# mcu.net
KiCad netlist of a schematic drawn in Altium Designer
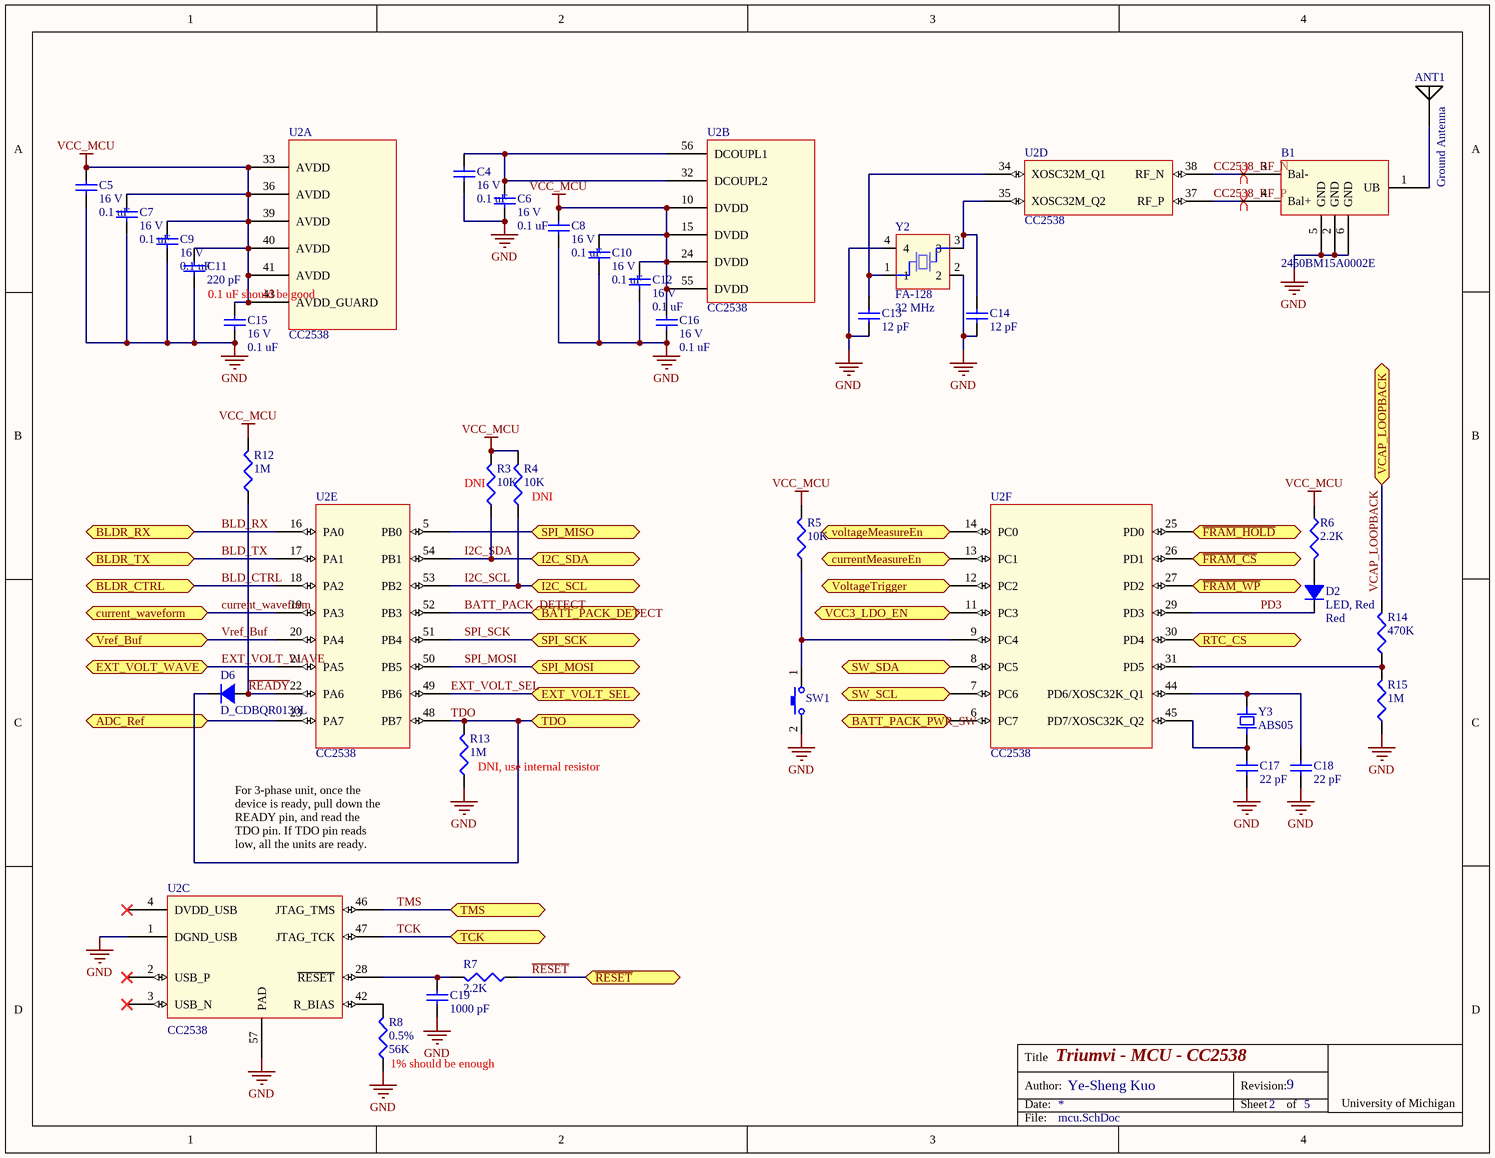
[diagram p0: mcu.SchDoc]

(export (version "E")
  (design (tool "Eeschema 10.0.6"))
  (components
    (comp (ref "ANT1")
      (value "Ground Antenna")
      (footprint "Chip Antenna")
      (description "2.4GHz Surface Mount Device (SMD) On Ground Antenna, 50 Ohms")
      (libsource (lib "RF") (part "Ground Antenna"))
    )
    (comp (ref "B1")
      (value "2450BM15A0002E")
      (footprint "2450BM15A0002")
      (description "2.45 GHz Balun for TI CC253X")
      (libsource (lib "RF") (part "2450BM15A0002E"))
    )
    (comp (ref "C4")
      (value "0.1 uF")
      (footprint "0402")
      (description "Ceramic capacitor, 0.1u, 16 V, 0402 package")
      (fields
        (field (name "VOLTAGE RATED") "16 V")
        (field (name "TOLERANCE") "10%")
        (field (name "Comment") "Ceramic capacitor")
      )
      (libsource (lib "rlc") (part "C_0.1u_16V_0402_ceramic"))
    )
    (comp (ref "C5")
      (value "0.1 uF")
      (footprint "0402")
      (description "Ceramic capacitor, 0.1u, 16 V, 0402 package")
      (fields
        (field (name "VOLTAGE RATED") "16 V")
        (field (name "TOLERANCE") "10%")
        (field (name "Comment") "Ceramic capacitor")
      )
      (libsource (lib "rlc") (part "C_0.1u_16V_0402_ceramic"))
    )
    (comp (ref "C6")
      (value "0.1 uF")
      (footprint "0402")
      (description "Ceramic capacitor, 0.1u, 16 V, 0402 package")
      (fields
        (field (name "VOLTAGE RATED") "16 V")
        (field (name "TOLERANCE") "10%")
        (field (name "Comment") "Ceramic capacitor")
      )
      (libsource (lib "rlc") (part "C_0.1u_16V_0402_ceramic"))
    )
    (comp (ref "C7")
      (value "0.1 uF")
      (footprint "0402")
      (description "Ceramic capacitor, 0.1u, 16 V, 0402 package")
      (fields
        (field (name "VOLTAGE RATED") "16 V")
        (field (name "TOLERANCE") "10%")
        (field (name "Comment") "Ceramic capacitor")
      )
      (libsource (lib "rlc") (part "C_0.1u_16V_0402_ceramic"))
    )
    (comp (ref "C8")
      (value "0.1 uF")
      (footprint "0402")
      (description "Ceramic capacitor, 0.1u, 16 V, 0402 package")
      (fields
        (field (name "VOLTAGE RATED") "16 V")
        (field (name "TOLERANCE") "10%")
        (field (name "Comment") "Ceramic capacitor")
      )
      (libsource (lib "rlc") (part "C_0.1u_16V_0402_ceramic"))
    )
    (comp (ref "C9")
      (value "0.1 uF")
      (footprint "0402")
      (description "Ceramic capacitor, 0.1u, 16 V, 0402 package")
      (fields
        (field (name "VOLTAGE RATED") "16 V")
        (field (name "TOLERANCE") "10%")
        (field (name "Comment") "Ceramic capacitor")
      )
      (libsource (lib "rlc") (part "C_0.1u_16V_0402_ceramic"))
    )
    (comp (ref "C10")
      (value "0.1 uF")
      (footprint "0402")
      (description "Ceramic capacitor, 0.1u, 16 V, 0402 package")
      (fields
        (field (name "VOLTAGE RATED") "16 V")
        (field (name "TOLERANCE") "10%")
        (field (name "Comment") "Ceramic capacitor")
      )
      (libsource (lib "rlc") (part "C_0.1u_16V_0402_ceramic"))
    )
    (comp (ref "C11")
      (value "220 pF")
      (footprint "0402")
      (description "Ceramic capacitor, 220 pF, 0402 package")
      (fields (field (name "TOLERANCE") "10%") (field (name "Comment") "Ceramic capacitor"))
      (libsource (lib "rlc") (part "C_220p_50V_0402_ceramic"))
    )
    (comp (ref "C12")
      (value "0.1 uF")
      (footprint "0402")
      (description "Ceramic capacitor, 0.1u, 16 V, 0402 package")
      (fields
        (field (name "VOLTAGE RATED") "16 V")
        (field (name "TOLERANCE") "10%")
        (field (name "Comment") "Ceramic capacitor")
      )
      (libsource (lib "rlc") (part "C_0.1u_16V_0402_ceramic"))
    )
    (comp (ref "C13")
      (value "12 pF")
      (footprint "0402")
      (description "Ceramic capacitor, 12 pF, 0402 package")
      (fields (field (name "TOLERANCE") "2%") (field (name "Comment") "Ceramic capacitor"))
      (libsource (lib "rlc") (part "C_12p_0402_ceramic"))
    )
    (comp (ref "C14")
      (value "12 pF")
      (footprint "0402")
      (description "Ceramic capacitor, 12 pF, 0402 package")
      (fields (field (name "TOLERANCE") "2%") (field (name "Comment") "Ceramic capacitor"))
      (libsource (lib "rlc") (part "C_12p_0402_ceramic"))
    )
    (comp (ref "C15")
      (value "0.1 uF")
      (footprint "0402")
      (description "Ceramic capacitor, 0.1u, 16 V, 0402 package")
      (fields
        (field (name "VOLTAGE RATED") "16 V")
        (field (name "TOLERANCE") "10%")
        (field (name "Comment") "Ceramic capacitor")
      )
      (libsource (lib "rlc") (part "C_0.1u_16V_0402_ceramic"))
    )
    (comp (ref "C16")
      (value "0.1 uF")
      (footprint "0402")
      (description "Ceramic capacitor, 0.1u, 16 V, 0402 package")
      (fields
        (field (name "VOLTAGE RATED") "16 V")
        (field (name "TOLERANCE") "10%")
        (field (name "Comment") "Ceramic capacitor")
      )
      (libsource (lib "rlc") (part "C_0.1u_16V_0402_ceramic"))
    )
    (comp (ref "C17")
      (value "22 pF")
      (footprint "0402")
      (description "Ceramic capacitor, 22 pF, 0402 package")
      (fields (field (name "TOLERANCE") "2%") (field (name "Comment") "Ceramic capacitor"))
      (libsource (lib "rlc") (part "C_22p_0402_ceramic"))
    )
    (comp (ref "C18")
      (value "22 pF")
      (footprint "0402")
      (description "Ceramic capacitor, 22 pF, 0402 package")
      (fields (field (name "TOLERANCE") "2%") (field (name "Comment") "Ceramic capacitor"))
      (libsource (lib "rlc") (part "C_22p_0402_ceramic"))
    )
    (comp (ref "C19")
      (value "1000 pF")
      (footprint "0402")
      (description "Ceramic capacitor, 1000 pF, 0402 package")
      (fields (field (name "TOLERANCE") "10%") (field (name "Comment") "Ceramic capacitor"))
      (libsource (lib "rlc") (part "C_1000p_50V_0402_ceramic"))
    )
    (comp (ref "D2")
      (value "LED, Red")
      (footprint "0402 - DIODE")
      (description "LED, Red, 0402")
      (fields (field (name "COLOR") "Red"))
      (libsource (lib "rlc") (part "D_LED_RED_0402"))
    )
    (comp (ref "D6")
      (value "D_CDBQR0130L")
      (footprint "0402 - DIODE")
      (description "SMD Schottky Barrier Diode")
      (libsource (lib "rlc") (part "D_CDBQR0130L"))
    )
    (comp (ref "R3")
      (value "10K")
      (footprint "0402")
      (description "Chip resistor, 10K, 0402 package")
      (fields (field (name "TOLERANCE") "1%") (field (name "POWER") "1/16 W"))
      (libsource (lib "rlc") (part "R_10K_0402"))
    )
    (comp (ref "R4")
      (value "10K")
      (footprint "0402")
      (description "Chip resistor, 10K, 0402 package")
      (fields (field (name "TOLERANCE") "1%") (field (name "POWER") "1/16 W"))
      (libsource (lib "rlc") (part "R_10K_0402"))
    )
    (comp (ref "R5")
      (value "10K")
      (footprint "0402")
      (description "Chip resistor, 10K, 0402 package")
      (fields (field (name "TOLERANCE") "1%") (field (name "POWER") "1/16 W"))
      (libsource (lib "rlc") (part "R_10K_0402"))
    )
    (comp (ref "R6")
      (value "2.2K")
      (footprint "0402")
      (description "Chip resistor, 2.2K, 0402 package")
      (fields (field (name "TOLERANCE") "1%") (field (name "POWER") "1/16 W"))
      (libsource (lib "rlc") (part "R_2.2K_0402"))
    )
    (comp (ref "R7")
      (value "2.2K")
      (footprint "0402")
      (description "Chip resistor, 2.2K, 0402 package")
      (fields (field (name "TOLERANCE") "1%") (field (name "POWER") "1/16 W"))
      (libsource (lib "rlc") (part "R_2.2K_0402"))
    )
    (comp (ref "R8")
      (value "56K")
      (footprint "0402")
      (description "Chip resistor, 56K, 0402 package")
      (fields
        (field (name "POWER") "1/16 W")
        (field (name "TOLERANCE") "0.5%")
        (field (name "Comment") "Chip resistor")
      )
      (libsource (lib "rlc") (part "R_56K_0402"))
    )
    (comp (ref "R12")
      (value "1M")
      (footprint "0402")
      (description "Chip resistor, 1M, 0402 package")
      (fields (field (name "TOLERANCE") "1%") (field (name "POWER") "1/16 W"))
      (libsource (lib "rlc") (part "R_1M_0402"))
    )
    (comp (ref "R13")
      (value "1M")
      (footprint "0402")
      (description "Chip resistor, 1M, 0402 package")
      (fields (field (name "TOLERANCE") "1%") (field (name "POWER") "1/16 W"))
      (libsource (lib "rlc") (part "R_1M_0402"))
    )
    (comp (ref "R14")
      (value "470K")
      (footprint "0402")
      (description "Chip resistor, 470K, 0402 package")
      (fields (field (name "TOLERANCE") "5%") (field (name "POWER") "1/16 W"))
      (libsource (lib "rlc") (part "R_470K_0402"))
    )
    (comp (ref "R15")
      (value "1M")
      (footprint "0402")
      (description "Chip resistor, 1M, 0402 package")
      (fields (field (name "TOLERANCE") "1%") (field (name "POWER") "1/16 W"))
      (libsource (lib "rlc") (part "R_1M_0402"))
    )
    (comp (ref "SW1")
      (value "EVQP7C")
      (footprint "EVQP7C")
      (description "3.5 mm×2.9 mm Side-operational SMD  Light Touch Switches")
      (libsource (lib "switches") (part "EVQP7C"))
    )
    (comp (ref "U2")
      (value "CC2538")
      (footprint "QFN56")
      (description "A Powerful System-On-Chip for 2.4-GHz IEEE 802.15.4, 6LoWPAN  and ZigBee Applications")
      (libsource (lib "mcu") (part "CC2538"))
    )
    (comp (ref "Y2")
      (value "FA-128")
      (footprint "FA-128")
      (description "MHz Range Crystal Unit")
      (fields (field (name "FREQUENCY") "32 MHz"))
      (libsource (lib "crystal_oscillators_rtc") (part "FA-128"))
    )
    (comp (ref "Y3")
      (value "ABS05")
      (footprint "ABS05")
      (description "32768 Hz SMD Low profile crystal")
      (libsource (lib "crystal_oscillators_rtc") (part "ABS05"))
    )
  )
  (nets
    (net (code "1") (name "/ADC_Ref") (class "Default")
      (node (ref "U2") (pin "23") (pinfunction "PA7_23") (pintype "bidirectional"))
    )
    (net (code "2") (name "/BATT_PACK_DETECT") (class "Default")
      (node (ref "U2") (pin "52") (pinfunction "PB3_52") (pintype "bidirectional"))
    )
    (net (code "3") (name "/BATT_PACK_PWR_SW") (class "Default")
      (node (ref "U2") (pin "6") (pinfunction "PC7_6") (pintype "bidirectional"))
    )
    (net (code "4") (name "/BLD_CTRL") (class "Default")
      (node (ref "U2") (pin "18") (pinfunction "PA2_18") (pintype "bidirectional"))
    )
    (net (code "5") (name "/BLD_RX") (class "Default")
      (node (ref "U2") (pin "16") (pinfunction "PA0_16") (pintype "bidirectional"))
    )
    (net (code "6") (name "/BLD_TX") (class "Default")
      (node (ref "U2") (pin "17") (pinfunction "PA1_17") (pintype "bidirectional"))
    )
    (net (code "7") (name "/CC2538_RF_N") (class "Default")
      (node (ref "B1") (pin "3") (pinfunction "Bal-_3") (pintype "passive"))
      (node (ref "U2") (pin "38") (pinfunction "RF_N_38") (pintype "bidirectional"))
    )
    (net (code "8") (name "/CC2538_RF_P") (class "Default")
      (node (ref "B1") (pin "4") (pinfunction "Bal+_4") (pintype "passive"))
      (node (ref "U2") (pin "37") (pinfunction "RF_P_37") (pintype "bidirectional"))
    )
    (net (code "9") (name "/EXT_VOLT_SEL") (class "Default")
      (node (ref "U2") (pin "49") (pinfunction "PB6_49") (pintype "bidirectional"))
    )
    (net (code "10") (name "/EXT_VOLT_WAVE") (class "Default")
      (node (ref "U2") (pin "21") (pinfunction "PA5_21") (pintype "bidirectional"))
    )
    (net (code "11") (name "/I2C_SCL") (class "Default")
      (node (ref "R4") (pin "2") (pintype "passive"))
      (node (ref "U2") (pin "53") (pinfunction "PB2_53") (pintype "bidirectional"))
    )
    (net (code "12") (name "/I2C_SDA") (class "Default")
      (node (ref "R3") (pin "2") (pintype "passive"))
      (node (ref "U2") (pin "54") (pinfunction "PB1_54") (pintype "bidirectional"))
    )
    (net (code "13") (name "/PD3") (class "Default")
      (node (ref "D2") (pin "2") (pintype "passive"))
      (node (ref "U2") (pin "29") (pinfunction "PD3_29") (pintype "bidirectional"))
    )
    (net (code "14") (name "/RTC_CS") (class "Default")
      (node (ref "U2") (pin "30") (pinfunction "PD4_30") (pintype "bidirectional"))
    )
    (net (code "15") (name "/SPI_MISO") (class "Default")
      (node (ref "U2") (pin "5") (pinfunction "PB0_5") (pintype "bidirectional"))
    )
    (net (code "16") (name "/SPI_MOSI") (class "Default")
      (node (ref "U2") (pin "50") (pinfunction "PB5_50") (pintype "bidirectional"))
    )
    (net (code "17") (name "/SPI_SCK") (class "Default")
      (node (ref "U2") (pin "51") (pinfunction "PB4_51") (pintype "bidirectional"))
    )
    (net (code "18") (name "/SW_SCL") (class "Default")
      (node (ref "U2") (pin "7") (pinfunction "PC6_7") (pintype "bidirectional"))
    )
    (net (code "19") (name "/SW_SDA") (class "Default")
      (node (ref "U2") (pin "8") (pinfunction "PC5_8") (pintype "bidirectional"))
    )
    (net (code "20") (name "/TCK") (class "Default")
      (node (ref "U2") (pin "47") (pinfunction "JTAG_TCK_47") (pintype "bidirectional"))
    )
    (net (code "21") (name "/TDO") (class "Default")
      (node (ref "D6") (pin "2") (pintype "passive"))
      (node (ref "R13") (pin "1") (pintype "passive"))
      (node (ref "U2") (pin "48") (pinfunction "PB7_48") (pintype "bidirectional"))
    )
    (net (code "22") (name "/TMS") (class "Default")
      (node (ref "U2") (pin "46") (pinfunction "JTAG_TMS_46") (pintype "bidirectional"))
    )
    (net (code "23") (name "/VCAP_LOOPBACK") (class "Default")
      (node (ref "R14") (pin "1") (pintype "passive"))
    )
    (net (code "24") (name "/VCC3_LDO_EN") (class "Default")
      (node (ref "U2") (pin "11") (pinfunction "PC3_11") (pintype "bidirectional"))
    )
    (net (code "25") (name "/VoltageTrigger") (class "Default")
      (node (ref "U2") (pin "12") (pinfunction "PC2_12") (pintype "bidirectional"))
    )
    (net (code "26") (name "/Vref_Buf") (class "Default")
      (node (ref "U2") (pin "20") (pinfunction "PA4_20") (pintype "bidirectional"))
    )
    (net (code "27") (name "/currentMeasureEn") (class "Default")
      (node (ref "U2") (pin "13") (pinfunction "PC1_13") (pintype "bidirectional"))
    )
    (net (code "28") (name "/current_waveform") (class "Default")
      (node (ref "U2") (pin "19") (pinfunction "PA3_19") (pintype "bidirectional"))
    )
    (net (code "29") (name "/voltageMeasureEn") (class "Default")
      (node (ref "U2") (pin "14") (pinfunction "PC0_14") (pintype "bidirectional"))
    )
    (net (code "30") (name "/~{FRAM_CS}") (class "Default")
      (node (ref "U2") (pin "26") (pinfunction "PD1_26") (pintype "bidirectional"))
    )
    (net (code "31") (name "/~{FRAM_HOLD}") (class "Default")
      (node (ref "U2") (pin "25") (pinfunction "PD0_25") (pintype "bidirectional"))
    )
    (net (code "32") (name "/~{FRAM_WP}") (class "Default")
      (node (ref "U2") (pin "27") (pinfunction "PD2_27") (pintype "bidirectional"))
    )
    (net (code "33") (name "/~{READY}") (class "Default")
      (node (ref "D6") (pin "1") (pintype "passive"))
      (node (ref "R12") (pin "2") (pintype "passive"))
      (node (ref "U2") (pin "22") (pinfunction "PA6_22") (pintype "bidirectional"))
    )
    (net (code "34") (name "/~{RESET}") (class "Default") (node (ref "R7") (pin "2") (pintype "passive")))
    (net (code "35") (name "GND") (class "Default")
      (node (ref "B1") (pin "2") (pinfunction "GND_2") (pintype "passive"))
      (node (ref "B1") (pin "5") (pinfunction "GND_5") (pintype "passive"))
      (node (ref "B1") (pin "6") (pinfunction "GND_6") (pintype "passive"))
      (node (ref "C10") (pin "2") (pintype "passive"))
      (node (ref "C11") (pin "2") (pintype "passive"))
      (node (ref "C12") (pin "2") (pintype "passive"))
      (node (ref "C13") (pin "1") (pintype "passive"))
      (node (ref "C14") (pin "1") (pintype "passive"))
      (node (ref "C15") (pin "2") (pintype "passive"))
      (node (ref "C16") (pin "2") (pintype "passive"))
      (node (ref "C17") (pin "2") (pintype "passive"))
      (node (ref "C18") (pin "2") (pintype "passive"))
      (node (ref "C19") (pin "2") (pintype "passive"))
      (node (ref "C4") (pin "2") (pintype "passive"))
      (node (ref "C5") (pin "2") (pintype "passive"))
      (node (ref "C6") (pin "2") (pintype "passive"))
      (node (ref "C7") (pin "2") (pintype "passive"))
      (node (ref "C8") (pin "2") (pintype "passive"))
      (node (ref "C9") (pin "2") (pintype "passive"))
      (node (ref "R13") (pin "2") (pintype "passive"))
      (node (ref "R15") (pin "2") (pintype "passive"))
      (node (ref "R8") (pin "2") (pintype "passive"))
      (node (ref "SW1") (pin "2") (pinfunction "2_2") (pintype "passive"))
      (node (ref "U2") (pin "1") (pinfunction "DGND_USB_1") (pintype "power_in"))
      (node (ref "U2") (pin "57") (pinfunction "PAD_57") (pintype "power_in"))
      (node (ref "Y2") (pin "2") (pinfunction "2_2") (pintype "passive"))
      (node (ref "Y2") (pin "4") (pinfunction "4_4") (pintype "passive"))
    )
    (net (code "36") (name "Net-(B1-UB)") (class "Default")
      (node (ref "ANT1") (pin "1") (pintype "passive"))
      (node (ref "B1") (pin "1") (pinfunction "UB_1") (pintype "passive"))
    )
    (net (code "37") (name "Net-(D2-Pad1)") (class "Default")
      (node (ref "D2") (pin "1") (pintype "passive"))
      (node (ref "R6") (pin "1") (pintype "passive"))
    )
    (net (code "38") (name "Net-(U2B-DCOUPL1)") (class "Default")
      (node (ref "C4") (pin "1") (pintype "passive"))
      (node (ref "C6") (pin "1") (pintype "passive"))
      (node (ref "U2") (pin "32") (pinfunction "DCOUPL2_32") (pintype "power_in"))
      (node (ref "U2") (pin "56") (pinfunction "DCOUPL1_56") (pintype "power_in"))
    )
    (net (code "39") (name "Net-(U2C-R_BIAS)") (class "Default")
      (node (ref "R8") (pin "1") (pintype "passive"))
      (node (ref "U2") (pin "42") (pinfunction "R_BIAS_42") (pintype "bidirectional"))
    )
    (net (code "40") (name "Net-(U2C-~{RESET})") (class "Default")
      (node (ref "C19") (pin "1") (pintype "passive"))
      (node (ref "R7") (pin "1") (pintype "passive"))
      (node (ref "U2") (pin "28") (pinfunction "~{RESET}_28") (pintype "bidirectional"))
    )
    (net (code "41") (name "Net-(U2D-XOSC32M_Q1)") (class "Default")
      (node (ref "C13") (pin "2") (pintype "passive"))
      (node (ref "U2") (pin "34") (pinfunction "XOSC32M_Q1_34") (pintype "bidirectional"))
      (node (ref "Y2") (pin "1") (pinfunction "1_1") (pintype "passive"))
    )
    (net (code "42") (name "Net-(U2D-XOSC32M_Q2)") (class "Default")
      (node (ref "C14") (pin "2") (pintype "passive"))
      (node (ref "U2") (pin "35") (pinfunction "XOSC32M_Q2_35") (pintype "bidirectional"))
      (node (ref "Y2") (pin "3") (pinfunction "3_3") (pintype "passive"))
    )
    (net (code "43") (name "Net-(U2F-PC4)") (class "Default")
      (node (ref "R5") (pin "2") (pintype "passive"))
      (node (ref "SW1") (pin "1") (pinfunction "1_1") (pintype "passive"))
      (node (ref "U2") (pin "9") (pinfunction "PC4_9") (pintype "bidirectional"))
    )
    (net (code "44") (name "Net-(U2F-PD5)") (class "Default")
      (node (ref "R14") (pin "2") (pintype "passive"))
      (node (ref "R15") (pin "1") (pintype "passive"))
      (node (ref "U2") (pin "31") (pinfunction "PD5_31") (pintype "bidirectional"))
    )
    (net (code "45") (name "Net-(U2F-PD6{slash}XOSC32K_Q1)") (class "Default")
      (node (ref "C18") (pin "1") (pintype "passive"))
      (node (ref "U2") (pin "44") (pinfunction "PD6/XOSC32K_Q1_44") (pintype "bidirectional"))
      (node (ref "Y3") (pin "1") (pintype "passive"))
    )
    (net (code "46") (name "Net-(U2F-PD7{slash}XOSC32K_Q2)") (class "Default")
      (node (ref "C17") (pin "1") (pintype "passive"))
      (node (ref "U2") (pin "45") (pinfunction "PD7/XOSC32K_Q2_45") (pintype "bidirectional"))
      (node (ref "Y3") (pin "2") (pintype "passive"))
    )
    (net (code "47") (name "VCC_MCU") (class "Default")
      (node (ref "C10") (pin "1") (pintype "passive"))
      (node (ref "C11") (pin "1") (pintype "passive"))
      (node (ref "C12") (pin "1") (pintype "passive"))
      (node (ref "C15") (pin "1") (pintype "passive"))
      (node (ref "C16") (pin "1") (pintype "passive"))
      (node (ref "C5") (pin "1") (pintype "passive"))
      (node (ref "C7") (pin "1") (pintype "passive"))
      (node (ref "C8") (pin "1") (pintype "passive"))
      (node (ref "C9") (pin "1") (pintype "passive"))
      (node (ref "R12") (pin "1") (pintype "passive"))
      (node (ref "R3") (pin "1") (pintype "passive"))
      (node (ref "R4") (pin "1") (pintype "passive"))
      (node (ref "R5") (pin "1") (pintype "passive"))
      (node (ref "R6") (pin "2") (pintype "passive"))
      (node (ref "U2") (pin "10") (pinfunction "DVDD_10") (pintype "power_in"))
      (node (ref "U2") (pin "15") (pinfunction "DVDD_15") (pintype "power_in"))
      (node (ref "U2") (pin "24") (pinfunction "DVDD_24") (pintype "power_in"))
      (node (ref "U2") (pin "33") (pinfunction "AVDD_33") (pintype "power_in"))
      (node (ref "U2") (pin "36") (pinfunction "AVDD_36") (pintype "power_in"))
      (node (ref "U2") (pin "39") (pinfunction "AVDD_39") (pintype "power_in"))
      (node (ref "U2") (pin "40") (pinfunction "AVDD_40") (pintype "power_in"))
      (node (ref "U2") (pin "41") (pinfunction "AVDD_41") (pintype "power_in"))
      (node (ref "U2") (pin "43") (pinfunction "AVDD_GUARD_43") (pintype "power_in"))
      (node (ref "U2") (pin "55") (pinfunction "DVDD_55") (pintype "power_in"))
    )
    (net (code "48") (name "unconnected-(U2C-DVDD_USB-Pad4)") (class "Default")
      (node (ref "U2") (pin "4") (pinfunction "DVDD_USB_4") (pintype "power_in+no_connect"))
    )
    (net (code "49") (name "unconnected-(U2C-USB_N-Pad3)") (class "Default")
      (node (ref "U2") (pin "3") (pinfunction "USB_N_3") (pintype "bidirectional+no_connect"))
    )
    (net (code "50") (name "unconnected-(U2C-USB_P-Pad2)") (class "Default")
      (node (ref "U2") (pin "2") (pinfunction "USB_P_2") (pintype "bidirectional+no_connect"))
    )
  )
)
